# Connectors.net
KiCad netlist of a schematic drawn in Altium Designer
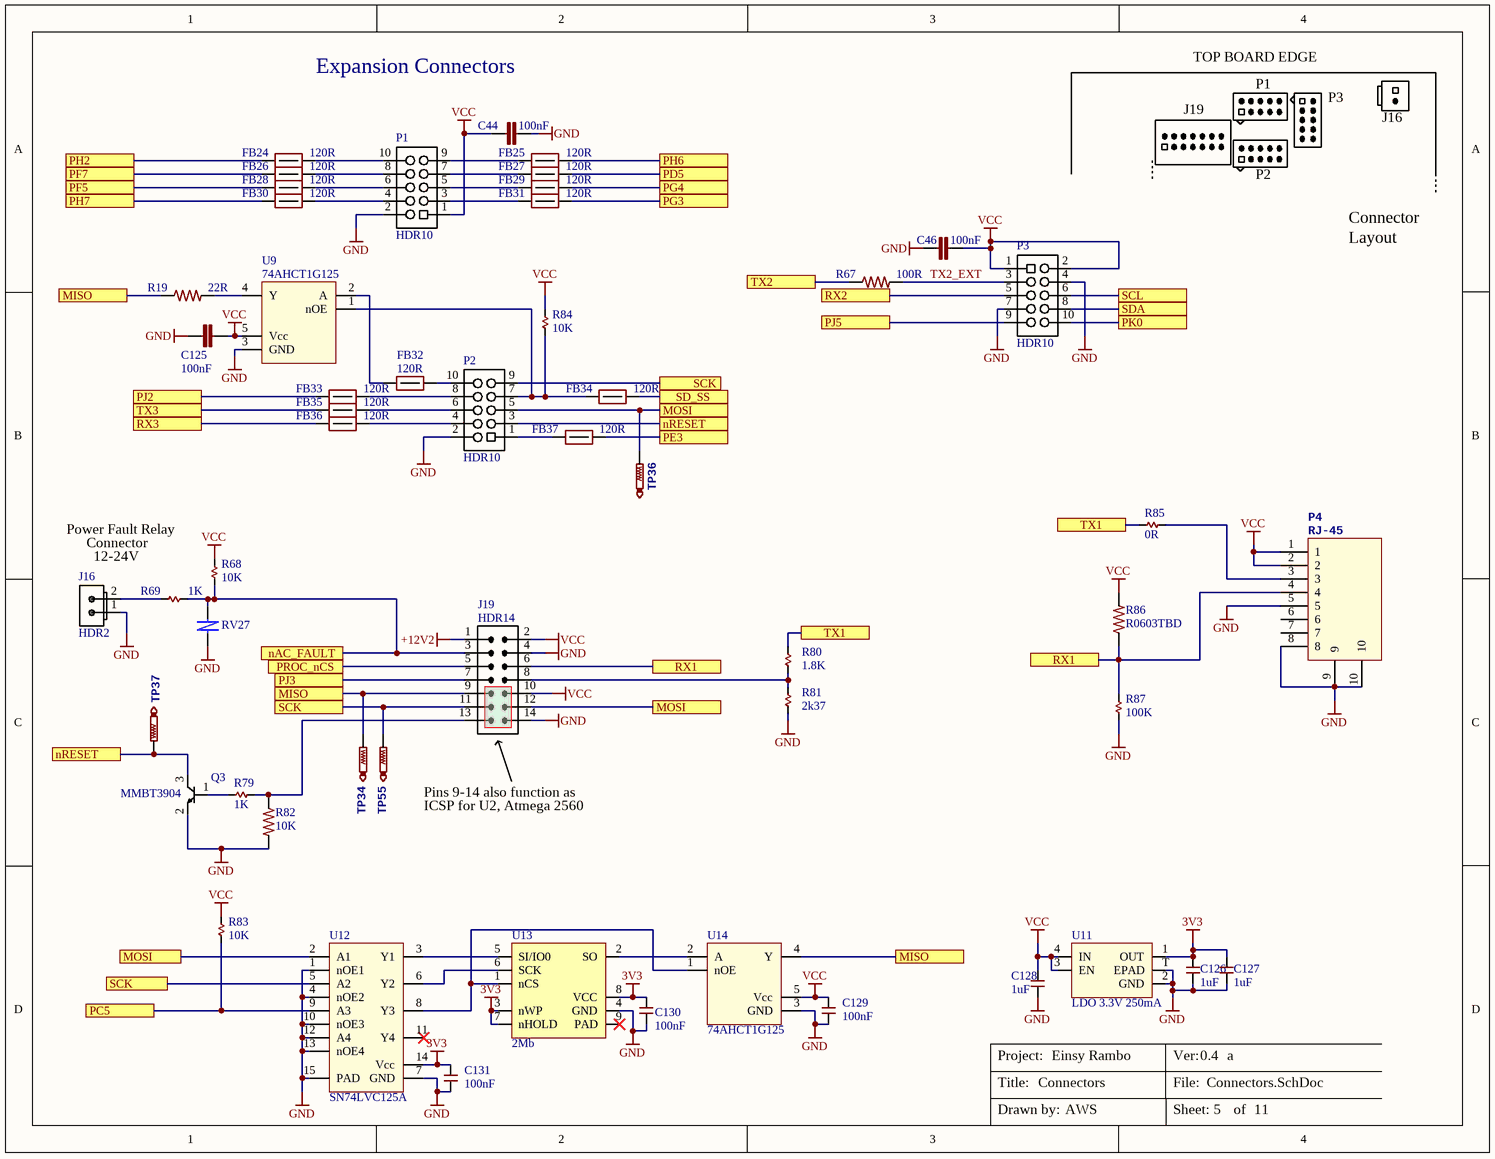
[diagram p0: Connectors.SchDoc]

(export (version "E")
  (design (tool "Eeschema 10.0.6"))
  (components
    (comp (ref "C44")
      (value "100nF")
      (footprint "C0402")
      (description "CAP CER 0402 100nF 16V 10% X7R")
      (fields (field (name "MANUFACTURER") "Murata") (field (name "TOLERANCE") "+/- 10%"))
      (libsource (lib "3Delight") (part "GRM155R71C104KA88D"))
    )
    (comp (ref "C46")
      (value "100nF")
      (footprint "C0402")
      (description "CAP CER 0402 100nF 16V 10% X7R")
      (fields (field (name "MANUFACTURER") "Murata") (field (name "TOLERANCE") "+/- 10%"))
      (libsource (lib "3Delight") (part "GRM155R71C104KA88D"))
    )
    (comp (ref "C125")
      (value "100nF")
      (footprint "C0402")
      (description "CAP CER 0402 100nF 16V 10% X7R")
      (fields (field (name "MANUFACTURER") "Murata") (field (name "TOLERANCE") "+/- 10%"))
      (libsource (lib "3Delight") (part "GRM155R71C104KA88D"))
    )
    (comp (ref "C126")
      (value "1uF")
      (footprint "C0402")
      (description "CAP CER 0402 1uF 6.3V 10% X5R")
      (fields (field (name "MANUFACTURER") "Murata") (field (name "PART") "1uF 6.3V X5R 0402"))
      (libsource (lib "Capacitors") (part "1uF 0402 6.3V X5R"))
    )
    (comp (ref "C127")
      (value "1uF")
      (footprint "C0402")
      (description "CAP CER 0402 1uF 6.3V 10% X5R")
      (fields (field (name "MANUFACTURER") "Murata") (field (name "PART") "1uF 6.3V X5R 0402"))
      (libsource (lib "Capacitors") (part "1uF 0402 6.3V X5R"))
    )
    (comp (ref "C128")
      (value "1uF")
      (footprint "C0402")
      (description "CAP CER 0402 1uF 6.3V 10% X5R")
      (fields (field (name "MANUFACTURER") "Murata") (field (name "PART") "1uF 6.3V X5R 0402"))
      (libsource (lib "Capacitors") (part "1uF 0402 6.3V X5R"))
    )
    (comp (ref "C129")
      (value "100nF")
      (footprint "C0402")
      (description "CAP CER 0402 100nF 16V 10% X7R")
      (fields (field (name "MANUFACTURER") "Murata") (field (name "PART") "0.1uF 16V X7R 0402"))
      (libsource (lib "Capacitors") (part "100nF 0402 16V X7R"))
    )
    (comp (ref "C130")
      (value "100nF")
      (footprint "C0402")
      (description "CAP CER 0402 100nF 16V 10% X7R")
      (fields (field (name "MANUFACTURER") "Murata") (field (name "PART") "0.1uF 16V X7R 0402"))
      (libsource (lib "Capacitors") (part "100nF 0402 16V X7R"))
    )
    (comp (ref "C131")
      (value "100nF")
      (footprint "C0402")
      (description "CAP CER 0402 100nF 16V 10% X7R")
      (fields (field (name "MANUFACTURER") "Murata") (field (name "PART") "0.1uF 16V X7R 0402"))
      (libsource (lib "Capacitors") (part "100nF 0402 16V X7R"))
    )
    (comp (ref "FB24")
      (value "120R")
      (footprint "R0402")
      (description "FERRITE BEAD 120 OHM 0402 1LN")
      (fields (field (name "MANUFACTURER") "Taiyo Yuden") (field (name "PART") "FERRITE 120R 1A 0402"))
      (libsource (lib "Inductors") (part "FERRITE 120R 1A 0402"))
    )
    (comp (ref "FB25")
      (value "120R")
      (footprint "R0402")
      (description "FERRITE BEAD 120 OHM 0402 1LN")
      (fields (field (name "MANUFACTURER") "Taiyo Yuden") (field (name "PART") "FERRITE 120R 1A 0402"))
      (libsource (lib "Inductors") (part "FERRITE 120R 1A 0402"))
    )
    (comp (ref "FB26")
      (value "120R")
      (footprint "R0402")
      (description "FERRITE BEAD 120 OHM 0402 1LN")
      (fields (field (name "MANUFACTURER") "Taiyo Yuden") (field (name "PART") "FERRITE 120R 1A 0402"))
      (libsource (lib "Inductors") (part "FERRITE 120R 1A 0402"))
    )
    (comp (ref "FB27")
      (value "120R")
      (footprint "R0402")
      (description "FERRITE BEAD 120 OHM 0402 1LN")
      (fields (field (name "MANUFACTURER") "Taiyo Yuden") (field (name "PART") "FERRITE 120R 1A 0402"))
      (libsource (lib "Inductors") (part "FERRITE 120R 1A 0402"))
    )
    (comp (ref "FB28")
      (value "120R")
      (footprint "R0402")
      (description "FERRITE BEAD 120 OHM 0402 1LN")
      (fields (field (name "MANUFACTURER") "Taiyo Yuden") (field (name "PART") "FERRITE 120R 1A 0402"))
      (libsource (lib "Inductors") (part "FERRITE 120R 1A 0402"))
    )
    (comp (ref "FB29")
      (value "120R")
      (footprint "R0402")
      (description "FERRITE BEAD 120 OHM 0402 1LN")
      (fields (field (name "MANUFACTURER") "Taiyo Yuden") (field (name "PART") "FERRITE 120R 1A 0402"))
      (libsource (lib "Inductors") (part "FERRITE 120R 1A 0402"))
    )
    (comp (ref "FB30")
      (value "120R")
      (footprint "R0402")
      (description "FERRITE BEAD 120 OHM 0402 1LN")
      (fields (field (name "MANUFACTURER") "Taiyo Yuden") (field (name "PART") "FERRITE 120R 1A 0402"))
      (libsource (lib "Inductors") (part "FERRITE 120R 1A 0402"))
    )
    (comp (ref "FB31")
      (value "120R")
      (footprint "R0402")
      (description "FERRITE BEAD 120 OHM 0402 1LN")
      (fields (field (name "MANUFACTURER") "Taiyo Yuden") (field (name "PART") "FERRITE 120R 1A 0402"))
      (libsource (lib "Inductors") (part "FERRITE 120R 1A 0402"))
    )
    (comp (ref "FB32")
      (value "120R")
      (footprint "R0402")
      (description "FERRITE BEAD 120 OHM 0402 1LN")
      (fields (field (name "MANUFACTURER") "Taiyo Yuden") (field (name "PART") "FERRITE 120R 1A 0402"))
      (libsource (lib "Inductors") (part "FERRITE 120R 1A 0402"))
    )
    (comp (ref "FB33")
      (value "120R")
      (footprint "R0402")
      (description "FERRITE BEAD 120 OHM 0402 1LN")
      (fields (field (name "MANUFACTURER") "Taiyo Yuden") (field (name "PART") "FERRITE 120R 1A 0402"))
      (libsource (lib "Inductors") (part "FERRITE 120R 1A 0402"))
    )
    (comp (ref "FB34")
      (value "120R")
      (footprint "R0402")
      (description "FERRITE BEAD 120 OHM 0402 1LN")
      (fields (field (name "MANUFACTURER") "Taiyo Yuden") (field (name "PART") "FERRITE 120R 1A 0402"))
      (libsource (lib "Inductors") (part "FERRITE 120R 1A 0402"))
    )
    (comp (ref "FB35")
      (value "120R")
      (footprint "R0402")
      (description "FERRITE BEAD 120 OHM 0402 1LN")
      (fields (field (name "MANUFACTURER") "Taiyo Yuden") (field (name "PART") "FERRITE 120R 1A 0402"))
      (libsource (lib "Inductors") (part "FERRITE 120R 1A 0402"))
    )
    (comp (ref "FB36")
      (value "120R")
      (footprint "R0402")
      (description "FERRITE BEAD 120 OHM 0402 1LN")
      (fields (field (name "MANUFACTURER") "Taiyo Yuden") (field (name "PART") "FERRITE 120R 1A 0402"))
      (libsource (lib "Inductors") (part "FERRITE 120R 1A 0402"))
    )
    (comp (ref "FB37")
      (value "120R")
      (footprint "R0402")
      (description "FERRITE BEAD 120 OHM 0402 1LN")
      (fields (field (name "MANUFACTURER") "Taiyo Yuden") (field (name "PART") "FERRITE 120R 1A 0402"))
      (libsource (lib "Inductors") (part "FERRITE 120R 1A 0402"))
    )
    (comp (ref "J16")
      (value "HDR2")
      (footprint "70543-02 PIN-IN-PASTE")
      (description "Connector 2pos")
      (fields (field (name "MANUFACTURER") "Molex") (field (name "PART") "2 Pin Conn"))
      (libsource (lib "Connectors") (part "CONN 2PIN VERT 0.1{dblquote} SHRD LOCKING PIN-IN-PASTE"))
    )
    (comp (ref "J19")
      (value "HDR14")
      (footprint "HDR2x7_SMT_BOT_ENTRY")
      (description "CONN RCPT DUAL ENTRY 14POS .100\"")
      (fields (field (name "MANUFACTURER") "TE Connectivity") (field (name "TOLERANCE") "-NA-"))
      (libsource (lib "Connectors") (part "CONN 14PIN 0.1{dblquote} FEMALE 2-ROW SMT BOT-ENTRY"))
    )
    (comp (ref "P1")
      (value "HDR10")
      (footprint "HDR2X5 IDC")
      (description "CONN HEADER VERT 10POS GOLD")
      (fields (field (name "MANUFACTURER") "On Shore") (field (name "TOLERANCE") "-NA-"))
      (libsource (lib "Connectors") (part "Header 10PIN 2ROW T-HOLE VERT SHROUDED"))
    )
    (comp (ref "P2")
      (value "HDR10")
      (footprint "HDR2X5 IDC")
      (description "CONN HEADER VERT 10POS GOLD")
      (fields (field (name "MANUFACTURER") "On Shore") (field (name "TOLERANCE") "-NA-"))
      (libsource (lib "Connectors") (part "Header 10PIN 2ROW T-HOLE VERT SHROUDED"))
    )
    (comp (ref "P3")
      (value "HDR10")
      (footprint "HDR2X5 IDC THIEVING")
      (description "CONN HEADER VERT 10POS GOLD")
      (fields (field (name "MANUFACTURER") "On Shore") (field (name "TOLERANCE") "-NA-"))
      (libsource (lib "") (part "Header 10PIN 2ROW T-HOLE VERT SHROUDED_1"))
    )
    (comp (ref "P4")
      (value "RJ-45")
      (description "CONN MOD JACK 8P8C R/A SHIELDED")
      (fields (field (name "MANUFACTURER") "Amphenol") (field (name "TOLERANCE") "NA"))
      (libsource (lib "Connectors") (part "RJ45 SMT"))
    )
    (comp (ref "Q3")
      (value "MMBT3904")
      (footprint "SOT523 SMALL")
      (description "TRANS NPN 60V 0.2A SOT523")
      (fields
        (field (name "MANUFACTURER") "Diodes Incorporated")
        (field (name "PART") "TRANS NPN 40V 0.2A SOT523")
      )
      (libsource (lib "Transistors") (part "MMBT3904_SOT523"))
    )
    (comp (ref "R19")
      (value "22R")
      (footprint "R0402")
      (description "RES 0402 22r 62.5mW 1%")
      (fields (field (name "MANUFACTURER") "Yageo") (field (name "TOLERANCE") "+/- 1%"))
      (libsource (lib "3Delight") (part "RC0402FR-0722RL"))
    )
    (comp (ref "R67")
      (value "100R")
      (footprint "R0402")
      (description "RES SMD 100 OHM 1% 1/16W 0402")
      (fields (field (name "MANUFACTURER") "Yageo") (field (name "PART") "100R 1% 0402"))
      (libsource (lib "Archim") (part "RES 100R 0402 1%"))
    )
    (comp (ref "R68")
      (value "10K")
      (footprint "R0402")
      (description "RES SMD 10K OHM 1% 1/16W 0402")
      (fields (field (name "MANUFACTURER") "Yageo") (field (name "PART") "10k 1% 0402"))
      (libsource (lib "Resistors") (part "10k 1% 0402"))
    )
    (comp (ref "R69")
      (value "1K")
      (footprint "R0402")
      (description "RES SMD 1K OHM 1% 1/16W 0402")
      (fields (field (name "MANUFACTURER") "Yageo") (field (name "PART") "1k"))
      (libsource (lib "3Delight") (part "RC0402FR-071KL"))
    )
    (comp (ref "R79")
      (value "1K")
      (footprint "R0402")
      (description "RES SMD 1K OHM 1% 1/16W 0402")
      (fields (field (name "MANUFACTURER") "Yageo") (field (name "PART") "1k"))
      (libsource (lib "3Delight") (part "RC0402FR-071KL"))
    )
    (comp (ref "R80")
      (value "1.8K")
      (footprint "R0402")
      (description "RES SMD 1.8K OHM 1% 1/16W 0402")
      (fields (field (name "MANUFACTURER") "Yageo") (field (name "PART") "1.8k"))
      (libsource (lib "3Delight") (part "RC0402FR-071K8L"))
    )
    (comp (ref "R81")
      (value "2k37")
      (footprint "R0402")
      (description "RES SMD 2.37K OHM 1% 1/16W 0402")
      (fields (field (name "MANUFACTURER") "Yageo") (field (name "PART") "2.37k"))
      (libsource (lib "3Delight") (part "RC0402FR-072K37L"))
    )
    (comp (ref "R82")
      (value "10K")
      (footprint "R0402")
      (description "RES SMD 10K OHM 1% 1/16W 0402")
      (fields (field (name "MANUFACTURER") "Yageo") (field (name "PART") "10k 1% 0402"))
      (libsource (lib "3Delight") (part "RC0402FR-0710KP"))
    )
    (comp (ref "R83")
      (value "10K")
      (footprint "R0402")
      (description "RES SMD 10K OHM 1% 1/16W 0402")
      (fields (field (name "MANUFACTURER") "Yageo") (field (name "PART") "10k 1% 0402"))
      (libsource (lib "Resistors") (part "10k 1% 0402"))
    )
    (comp (ref "R84")
      (value "10K")
      (footprint "R0402")
      (description "RES SMD 10K OHM 1% 1/16W 0402")
      (fields (field (name "MANUFACTURER") "Yageo") (field (name "PART") "10k 1% 0402"))
      (libsource (lib "Resistors") (part "10k 1% 0402"))
    )
    (comp (ref "R85")
      (value "0R")
      (footprint "R0603")
      (description "RES SMD 0.0OHM JUMPER 1/10W 0603")
      (fields (field (name "MANUFACTURER") "Bourns") (field (name "TOLERANCE") "-NA-"))
      (libsource (lib "Resistors") (part "0R 0603"))
    )
    (comp (ref "R86")
      (value "R0603TBD")
      (footprint "R0603")
      (description "Resistor")
      (fields (field (name "PUBLISHER") "UltiMachine"))
      (libsource (lib "3Delight") (part "R0603TBD"))
    )
    (comp (ref "R87")
      (value "100K")
      (footprint "Passives:R0603")
      (description "RES SMD 100K OHM 1% 1/10W 0603")
      (fields (field (name "MANUFACTURER") "Panasonic") (field (name "PART") "100k 1% 0603"))
      (libsource (lib "Resistors") (part "100k 1% 0603"))
    )
    (comp (ref "RV27")
      (value "VRS0402SR55R101N")
      (footprint "C0402")
      (description "Multi-Layer Varistor")
      (fields (field (name "MANUFACTURER") "Yageo") (field (name "PART") "12V"))
      (libsource (lib "3Delight") (part "VRS0402SR55R101N"))
    )
    (comp (ref "TP34")
      (value "TestPoint")
      (footprint "TP1-27")
      (description "Test Point")
      (libsource (lib "3Delight") (part "TestPoint"))
    )
    (comp (ref "TP36")
      (value "TestPoint")
      (footprint "TP1-27")
      (description "Test Point")
      (libsource (lib "3Delight") (part "TestPoint"))
    )
    (comp (ref "TP37")
      (value "TestPoint")
      (footprint "TP1-27")
      (description "Test Point")
      (libsource (lib "") (part "TestPoint_1"))
    )
    (comp (ref "TP55")
      (value "TestPoint")
      (footprint "TP1-27")
      (description "Test Point")
      (libsource (lib "3Delight") (part "TestPoint"))
    )
    (comp (ref "U9")
      (value "74AHCT1G125")
      (footprint "SOTFL50P160X60-5L")
      (description "IC BUS BUFF TRI-ST N-INV  SOT-553")
      (fields (field (name "TOLERANCE") "-NA-") (field (name "MANUFACTURER") "TI"))
      (libsource (lib "") (part "SN74AHCT1G125DRLR_1"))
    )
    (comp (ref "U11")
      (value "LDO 3.3V 250mA")
      (footprint "XDFN4 1X1")
      (description "IC REG LINEAR 3.3V 250MA 4XDFN")
      (fields (field (name "MANUFACTURER") "On Semi") (field (name "TOLERANCE") "-NA-"))
      (libsource (lib "ICs-Power") (part "LDO 3.3V 250mA"))
    )
    (comp (ref "U12")
      (value "SN74LVC125A")
      (footprint "PVQFN14_3.5X3.5")
      (description "IC BUS BUFF TRI-ST QD 14VQFN")
      (fields (field (name "TOLERANCE") "-NA-") (field (name "MANUFACTURER") "TI"))
      (libsource (lib "ICs-Logic") (part "SN74LVC125A"))
    )
    (comp (ref "U13")
      (value "2Mb")
      (footprint "USON8 2X3")
      (description "IC FLASH 2MBIT 104MHZ 8USON")
      (fields (field (name "MANUFACTURER") "Winbond") (field (name "TOLERANCE") "-NA-"))
      (libsource (lib "ICs-uC") (part "W25X20CL"))
    )
    (comp (ref "U14")
      (value "74AHCT1G125")
      (footprint "SOTFL50P160X60-5L")
      (description "IC BUS BUFF TRI-ST N-INV  SOT-553")
      (fields (field (name "TOLERANCE") "-NA-") (field (name "MANUFACTURER") "TI"))
      (libsource (lib "ICs-Logic") (part "SN74AHCT1G125DRLR"))
    )
  )
  (nets
    (net (code "1") (name "+12V2") (class "Default")
      (node (ref "J19") (pin "1") (pinfunction "S_1") (pintype "passive"))
    )
    (net (code "2") (name "/MISO") (class "Default")
      (node (ref "J19") (pin "9") (pinfunction "S_9") (pintype "passive"))
      (node (ref "R19") (pin "1") (pinfunction "1_1") (pintype "passive"))
      (node (ref "TP34") (pin "TP") (pinfunction "TP_TP") (pintype "passive"))
      (node (ref "U14") (pin "4") (pinfunction "Y_4") (pintype "passive"))
    )
    (net (code "3") (name "/MOSI") (class "Default")
      (node (ref "J19") (pin "12") (pinfunction "S_12") (pintype "passive"))
      (node (ref "P2") (pin "5") (pinfunction "5_5") (pintype "passive"))
      (node (ref "TP36") (pin "TP") (pinfunction "TP_TP") (pintype "passive"))
      (node (ref "U12") (pin "2") (pinfunction "A1_2") (pintype "passive"))
    )
    (net (code "4") (name "/PC5") (class "Default")
      (node (ref "R83") (pin "2") (pinfunction "2_2") (pintype "passive"))
      (node (ref "U12") (pin "9") (pinfunction "A3_9") (pintype "passive"))
    )
    (net (code "5") (name "/PD5") (class "Default")
      (node (ref "FB27") (pin "2") (pinfunction "2_2") (pintype "passive"))
    )
    (net (code "6") (name "/PE3") (class "Default")
      (node (ref "FB37") (pin "2") (pinfunction "2_2") (pintype "passive"))
    )
    (net (code "7") (name "/PF5") (class "Default")
      (node (ref "FB28") (pin "1") (pinfunction "1_1") (pintype "passive"))
    )
    (net (code "8") (name "/PF7") (class "Default")
      (node (ref "FB26") (pin "1") (pinfunction "1_1") (pintype "passive"))
    )
    (net (code "9") (name "/PG3") (class "Default")
      (node (ref "FB31") (pin "2") (pinfunction "2_2") (pintype "passive"))
    )
    (net (code "10") (name "/PG4") (class "Default")
      (node (ref "FB29") (pin "2") (pinfunction "2_2") (pintype "passive"))
    )
    (net (code "11") (name "/PH2") (class "Default")
      (node (ref "FB24") (pin "1") (pinfunction "1_1") (pintype "passive"))
    )
    (net (code "12") (name "/PH6") (class "Default")
      (node (ref "FB25") (pin "2") (pinfunction "2_2") (pintype "passive"))
    )
    (net (code "13") (name "/PH7") (class "Default")
      (node (ref "FB30") (pin "1") (pinfunction "1_1") (pintype "passive"))
    )
    (net (code "14") (name "/PJ2") (class "Default")
      (node (ref "FB33") (pin "1") (pinfunction "1_1") (pintype "passive"))
    )
    (net (code "15") (name "/PJ3") (class "Default")
      (node (ref "J19") (pin "7") (pinfunction "S_7") (pintype "passive"))
    )
    (net (code "16") (name "/PJ5") (class "Default")
      (node (ref "P3") (pin "9") (pinfunction "9_9") (pintype "passive"))
    )
    (net (code "17") (name "/PK0") (class "Default")
      (node (ref "P3") (pin "10") (pinfunction "10_10") (pintype "passive"))
    )
    (net (code "18") (name "/PROC_nCS") (class "Default")
      (node (ref "J19") (pin "5") (pinfunction "S_5") (pintype "passive"))
    )
    (net (code "19") (name "/RX1") (class "Default")
      (node (ref "J19") (pin "6") (pinfunction "S_6") (pintype "passive"))
      (node (ref "P4") (pin "4") (pinfunction "4_4") (pintype "passive"))
      (node (ref "R86") (pin "1") (pinfunction "1_1") (pintype "passive"))
      (node (ref "R87") (pin "2") (pinfunction "2_2") (pintype "passive"))
    )
    (net (code "20") (name "/RX2") (class "Default")
      (node (ref "P3") (pin "5") (pinfunction "5_5") (pintype "passive"))
    )
    (net (code "21") (name "/RX3") (class "Default")
      (node (ref "FB36") (pin "1") (pinfunction "1_1") (pintype "passive"))
    )
    (net (code "22") (name "/SCK") (class "Default")
      (node (ref "J19") (pin "11") (pinfunction "S_11") (pintype "passive"))
      (node (ref "P2") (pin "9") (pinfunction "9_9") (pintype "passive"))
      (node (ref "TP55") (pin "TP") (pinfunction "TP_TP") (pintype "passive"))
      (node (ref "U12") (pin "5") (pinfunction "A2_5") (pintype "passive"))
    )
    (net (code "23") (name "/SCL") (class "Default")
      (node (ref "P3") (pin "6") (pinfunction "6_6") (pintype "passive"))
    )
    (net (code "24") (name "/SDA") (class "Default")
      (node (ref "P3") (pin "8") (pinfunction "8_8") (pintype "passive"))
    )
    (net (code "25") (name "/SD_SS") (class "Default")
      (node (ref "FB34") (pin "2") (pinfunction "2_2") (pintype "passive"))
    )
    (net (code "26") (name "/TX1") (class "Default")
      (node (ref "R80") (pin "1") (pinfunction "1_1") (pintype "passive"))
      (node (ref "R85") (pin "1") (pinfunction "1_1") (pintype "passive"))
    )
    (net (code "27") (name "/TX2") (class "Default")
      (node (ref "R67") (pin "1") (pinfunction "1_1") (pintype "passive"))
    )
    (net (code "28") (name "/TX2_EXT") (class "Default")
      (node (ref "P3") (pin "3") (pinfunction "3_3") (pintype "passive"))
      (node (ref "R67") (pin "2") (pinfunction "2_2") (pintype "passive"))
    )
    (net (code "29") (name "/TX3") (class "Default")
      (node (ref "FB35") (pin "1") (pinfunction "1_1") (pintype "passive"))
    )
    (net (code "30") (name "/nAC_FAULT") (class "Default")
      (node (ref "J19") (pin "3") (pinfunction "S_3") (pintype "passive"))
      (node (ref "R68") (pin "1") (pinfunction "1_1") (pintype "passive"))
      (node (ref "R69") (pin "2") (pinfunction "2_2") (pintype "passive"))
      (node (ref "RV27") (pin "2") (pinfunction "2_2") (pintype "passive"))
    )
    (net (code "31") (name "/nRESET") (class "Default")
      (node (ref "P2") (pin "3") (pinfunction "3_3") (pintype "passive"))
      (node (ref "Q3") (pin "3") (pinfunction "C_3") (pintype "power_in"))
      (node (ref "TP37") (pin "TP") (pinfunction "TP_TP") (pintype "passive"))
    )
    (net (code "32") (name "3V3") (class "Default")
      (node (ref "C126") (pin "2") (pinfunction "2_2") (pintype "passive"))
      (node (ref "C127") (pin "2") (pinfunction "2_2") (pintype "passive"))
      (node (ref "C130") (pin "2") (pinfunction "2_2") (pintype "passive"))
      (node (ref "C131") (pin "1") (pinfunction "1_1") (pintype "passive"))
      (node (ref "U11") (pin "1") (pinfunction "OUT_1") (pintype "power_in"))
      (node (ref "U12") (pin "14") (pinfunction "Vcc_14") (pintype "passive"))
      (node (ref "U13") (pin "3") (pinfunction "nWP_3") (pintype "passive"))
      (node (ref "U13") (pin "7") (pinfunction "nHOLD_7") (pintype "passive"))
      (node (ref "U13") (pin "8") (pinfunction "VCC_8") (pintype "passive"))
    )
    (net (code "33") (name "GND") (class "Default")
      (node (ref "C125") (pin "1") (pinfunction "1_1") (pintype "passive"))
      (node (ref "C126") (pin "1") (pinfunction "1_1") (pintype "passive"))
      (node (ref "C127") (pin "1") (pinfunction "1_1") (pintype "passive"))
      (node (ref "C128") (pin "1") (pinfunction "1_1") (pintype "passive"))
      (node (ref "C129") (pin "1") (pinfunction "1_1") (pintype "passive"))
      (node (ref "C130") (pin "1") (pinfunction "1_1") (pintype "passive"))
      (node (ref "C131") (pin "2") (pinfunction "2_2") (pintype "passive"))
      (node (ref "C44") (pin "2") (pinfunction "2_2") (pintype "passive"))
      (node (ref "C46") (pin "1") (pinfunction "1_1") (pintype "passive"))
      (node (ref "J16") (pin "1") (pinfunction "S_1") (pintype "passive"))
      (node (ref "J19") (pin "14") (pinfunction "S_14") (pintype "passive"))
      (node (ref "J19") (pin "4") (pinfunction "S_4") (pintype "passive"))
      (node (ref "P1") (pin "2") (pinfunction "2_2") (pintype "passive"))
      (node (ref "P2") (pin "2") (pinfunction "2_2") (pintype "passive"))
      (node (ref "P3") (pin "4") (pinfunction "4_4") (pintype "passive"))
      (node (ref "P3") (pin "7") (pinfunction "7_7") (pintype "passive"))
      (node (ref "P4") (pin "10") (pinfunction "10_10") (pintype "passive"))
      (node (ref "P4") (pin "5") (pinfunction "5_5") (pintype "passive"))
      (node (ref "P4") (pin "8") (pinfunction "8_8") (pintype "passive"))
      (node (ref "P4") (pin "9") (pinfunction "9_9") (pintype "passive"))
      (node (ref "Q3") (pin "2") (pinfunction "E_2") (pintype "power_in"))
      (node (ref "R81") (pin "2") (pinfunction "2_2") (pintype "passive"))
      (node (ref "R82") (pin "2") (pinfunction "2_2") (pintype "passive"))
      (node (ref "R87") (pin "1") (pinfunction "1_1") (pintype "passive"))
      (node (ref "RV27") (pin "1") (pinfunction "1_1") (pintype "passive"))
      (node (ref "U11") (pin "2") (pinfunction "GND_2") (pintype "power_in"))
      (node (ref "U11") (pin "T") (pinfunction "EPAD_T") (pintype "power_in"))
      (node (ref "U12") (pin "1") (pinfunction "nOE1_1") (pintype "passive"))
      (node (ref "U12") (pin "10") (pinfunction "nOE3_10") (pintype "passive"))
      (node (ref "U12") (pin "12") (pinfunction "A4_12") (pintype "passive"))
      (node (ref "U12") (pin "13") (pinfunction "nOE4_13") (pintype "passive"))
      (node (ref "U12") (pin "15") (pinfunction "PAD_15") (pintype "passive"))
      (node (ref "U12") (pin "4") (pinfunction "nOE2_4") (pintype "passive"))
      (node (ref "U12") (pin "7") (pinfunction "GND_7") (pintype "passive"))
      (node (ref "U13") (pin "4") (pinfunction "GND_4") (pintype "passive"))
      (node (ref "U14") (pin "3") (pinfunction "GND_3") (pintype "passive"))
      (node (ref "U9") (pin "3") (pinfunction "GND_3") (pintype "passive"))
    )
    (net (code "34") (name "Net-(FB24-Pad2)") (class "Default")
      (node (ref "FB24") (pin "2") (pinfunction "2_2") (pintype "passive"))
      (node (ref "P1") (pin "10") (pinfunction "10_10") (pintype "passive"))
    )
    (net (code "35") (name "Net-(FB25-Pad1)") (class "Default")
      (node (ref "FB25") (pin "1") (pinfunction "1_1") (pintype "passive"))
      (node (ref "P1") (pin "9") (pinfunction "9_9") (pintype "passive"))
    )
    (net (code "36") (name "Net-(FB26-Pad2)") (class "Default")
      (node (ref "FB26") (pin "2") (pinfunction "2_2") (pintype "passive"))
      (node (ref "P1") (pin "8") (pinfunction "8_8") (pintype "passive"))
    )
    (net (code "37") (name "Net-(FB27-Pad1)") (class "Default")
      (node (ref "FB27") (pin "1") (pinfunction "1_1") (pintype "passive"))
      (node (ref "P1") (pin "7") (pinfunction "7_7") (pintype "passive"))
    )
    (net (code "38") (name "Net-(FB28-Pad2)") (class "Default")
      (node (ref "FB28") (pin "2") (pinfunction "2_2") (pintype "passive"))
      (node (ref "P1") (pin "6") (pinfunction "6_6") (pintype "passive"))
    )
    (net (code "39") (name "Net-(FB29-Pad1)") (class "Default")
      (node (ref "FB29") (pin "1") (pinfunction "1_1") (pintype "passive"))
      (node (ref "P1") (pin "5") (pinfunction "5_5") (pintype "passive"))
    )
    (net (code "40") (name "Net-(FB30-Pad2)") (class "Default")
      (node (ref "FB30") (pin "2") (pinfunction "2_2") (pintype "passive"))
      (node (ref "P1") (pin "4") (pinfunction "4_4") (pintype "passive"))
    )
    (net (code "41") (name "Net-(FB31-Pad1)") (class "Default")
      (node (ref "FB31") (pin "1") (pinfunction "1_1") (pintype "passive"))
      (node (ref "P1") (pin "3") (pinfunction "3_3") (pintype "passive"))
    )
    (net (code "42") (name "Net-(FB32-Pad2)") (class "Default")
      (node (ref "FB32") (pin "2") (pinfunction "2_2") (pintype "passive"))
      (node (ref "P2") (pin "10") (pinfunction "10_10") (pintype "passive"))
    )
    (net (code "43") (name "Net-(FB33-Pad2)") (class "Default")
      (node (ref "FB33") (pin "2") (pinfunction "2_2") (pintype "passive"))
      (node (ref "P2") (pin "8") (pinfunction "8_8") (pintype "passive"))
    )
    (net (code "44") (name "Net-(FB35-Pad2)") (class "Default")
      (node (ref "FB35") (pin "2") (pinfunction "2_2") (pintype "passive"))
      (node (ref "P2") (pin "6") (pinfunction "6_6") (pintype "passive"))
    )
    (net (code "45") (name "Net-(FB36-Pad2)") (class "Default")
      (node (ref "FB36") (pin "2") (pinfunction "2_2") (pintype "passive"))
      (node (ref "P2") (pin "4") (pinfunction "4_4") (pintype "passive"))
    )
    (net (code "46") (name "Net-(FB37-Pad1)") (class "Default")
      (node (ref "FB37") (pin "1") (pinfunction "1_1") (pintype "passive"))
      (node (ref "P2") (pin "1") (pinfunction "1_1") (pintype "passive"))
    )
    (net (code "47") (name "Net-(J16-S-Pad2)") (class "Default")
      (node (ref "J16") (pin "2") (pinfunction "S_2") (pintype "passive"))
      (node (ref "R69") (pin "1") (pinfunction "1_1") (pintype "passive"))
    )
    (net (code "48") (name "Net-(J19-S-Pad8)") (class "Default")
      (node (ref "J19") (pin "8") (pinfunction "S_8") (pintype "passive"))
      (node (ref "R80") (pin "2") (pinfunction "2_2") (pintype "passive"))
      (node (ref "R81") (pin "1") (pinfunction "1_1") (pintype "passive"))
    )
    (net (code "49") (name "Net-(J19-S-Pad13)") (class "Default")
      (node (ref "J19") (pin "13") (pinfunction "S_13") (pintype "passive"))
      (node (ref "R79") (pin "1") (pinfunction "1_1") (pintype "passive"))
      (node (ref "R82") (pin "1") (pinfunction "1_1") (pintype "passive"))
    )
    (net (code "50") (name "Net-(P4-Pad3)") (class "Default")
      (node (ref "P4") (pin "3") (pinfunction "3_3") (pintype "passive"))
      (node (ref "R85") (pin "2") (pinfunction "2_2") (pintype "passive"))
    )
    (net (code "51") (name "Net-(Q3-B)") (class "Default")
      (node (ref "Q3") (pin "1") (pinfunction "B_1") (pintype "power_in"))
      (node (ref "R79") (pin "2") (pinfunction "2_2") (pintype "passive"))
    )
    (net (code "52") (name "Net-(U9-A)") (class "Default")
      (node (ref "FB32") (pin "1") (pinfunction "1_1") (pintype "passive"))
      (node (ref "U9") (pin "2") (pinfunction "A_2") (pintype "passive"))
    )
    (net (code "53") (name "Net-(U9-Y)") (class "Default")
      (node (ref "R19") (pin "2") (pinfunction "2_2") (pintype "passive"))
      (node (ref "U9") (pin "4") (pinfunction "Y_4") (pintype "passive"))
    )
    (net (code "54") (name "Net-(U9-nOE)") (class "Default")
      (node (ref "FB34") (pin "1") (pinfunction "1_1") (pintype "passive"))
      (node (ref "P2") (pin "7") (pinfunction "7_7") (pintype "passive"))
      (node (ref "R84") (pin "1") (pinfunction "1_1") (pintype "passive"))
      (node (ref "U9") (pin "1") (pinfunction "nOE_1") (pintype "passive"))
    )
    (net (code "55") (name "Net-(U12-Y1)") (class "Default")
      (node (ref "U12") (pin "3") (pinfunction "Y1_3") (pintype "passive"))
      (node (ref "U13") (pin "5") (pinfunction "SI/IO0_5") (pintype "passive"))
    )
    (net (code "56") (name "Net-(U12-Y2)") (class "Default")
      (node (ref "U12") (pin "6") (pinfunction "Y2_6") (pintype "passive"))
      (node (ref "U13") (pin "6") (pinfunction "SCK_6") (pintype "passive"))
    )
    (net (code "57") (name "Net-(U12-Y3)") (class "Default")
      (node (ref "U12") (pin "8") (pinfunction "Y3_8") (pintype "passive"))
      (node (ref "U13") (pin "1") (pinfunction "nCS_1") (pintype "passive"))
      (node (ref "U14") (pin "1") (pinfunction "nOE_1") (pintype "passive"))
    )
    (net (code "58") (name "Net-(U13-SO)") (class "Default")
      (node (ref "U13") (pin "2") (pinfunction "SO_2") (pintype "passive"))
      (node (ref "U14") (pin "2") (pinfunction "A_2") (pintype "passive"))
    )
    (net (code "59") (name "VCC") (class "Default")
      (node (ref "C125") (pin "2") (pinfunction "2_2") (pintype "passive"))
      (node (ref "C128") (pin "2") (pinfunction "2_2") (pintype "passive"))
      (node (ref "C129") (pin "2") (pinfunction "2_2") (pintype "passive"))
      (node (ref "C44") (pin "1") (pinfunction "1_1") (pintype "passive"))
      (node (ref "C46") (pin "2") (pinfunction "2_2") (pintype "passive"))
      (node (ref "J19") (pin "10") (pinfunction "S_10") (pintype "passive"))
      (node (ref "J19") (pin "2") (pinfunction "S_2") (pintype "passive"))
      (node (ref "P1") (pin "1") (pinfunction "1_1") (pintype "passive"))
      (node (ref "P3") (pin "1") (pinfunction "1_1") (pintype "passive"))
      (node (ref "P3") (pin "2") (pinfunction "2_2") (pintype "passive"))
      (node (ref "P4") (pin "1") (pinfunction "1_1") (pintype "passive"))
      (node (ref "P4") (pin "2") (pinfunction "2_2") (pintype "passive"))
      (node (ref "R68") (pin "2") (pinfunction "2_2") (pintype "passive"))
      (node (ref "R83") (pin "1") (pinfunction "1_1") (pintype "passive"))
      (node (ref "R84") (pin "2") (pinfunction "2_2") (pintype "passive"))
      (node (ref "R86") (pin "2") (pinfunction "2_2") (pintype "passive"))
      (node (ref "U11") (pin "3") (pinfunction "EN_3") (pintype "power_in"))
      (node (ref "U11") (pin "4") (pinfunction "IN_4") (pintype "power_in"))
      (node (ref "U14") (pin "5") (pinfunction "Vcc_5") (pintype "passive"))
      (node (ref "U9") (pin "5") (pinfunction "Vcc_5") (pintype "passive"))
    )
    (net (code "60") (name "unconnected-(P4-Pad6)") (class "Default")
      (node (ref "P4") (pin "6") (pinfunction "6_6") (pintype "passive"))
    )
    (net (code "61") (name "unconnected-(P4-Pad7)") (class "Default")
      (node (ref "P4") (pin "7") (pinfunction "7_7") (pintype "passive"))
    )
    (net (code "62") (name "unconnected-(U9-NC-Pad23)") (class "Default")
      (node (ref "U9") (pin "23") (pinfunction "NC_23") (pintype "passive"))
    )
    (net (code "63") (name "unconnected-(U12-NC-Pad23)") (class "Default")
      (node (ref "U12") (pin "23") (pinfunction "NC_23") (pintype "passive"))
    )
    (net (code "64") (name "unconnected-(U12-Y4-Pad11)") (class "Default")
      (node (ref "U12") (pin "11") (pinfunction "Y4_11") (pintype "passive+no_connect"))
    )
    (net (code "65") (name "unconnected-(U13-PAD-Pad9)") (class "Default")
      (node (ref "U13") (pin "9") (pinfunction "PAD_9") (pintype "passive+no_connect"))
    )
    (net (code "66") (name "unconnected-(U14-NC-Pad23)") (class "Default")
      (node (ref "U14") (pin "23") (pinfunction "NC_23") (pintype "passive"))
    )
  )
)
